# 1_P1_schdoc.net
KiCad netlist of a schematic drawn in Altium Designer
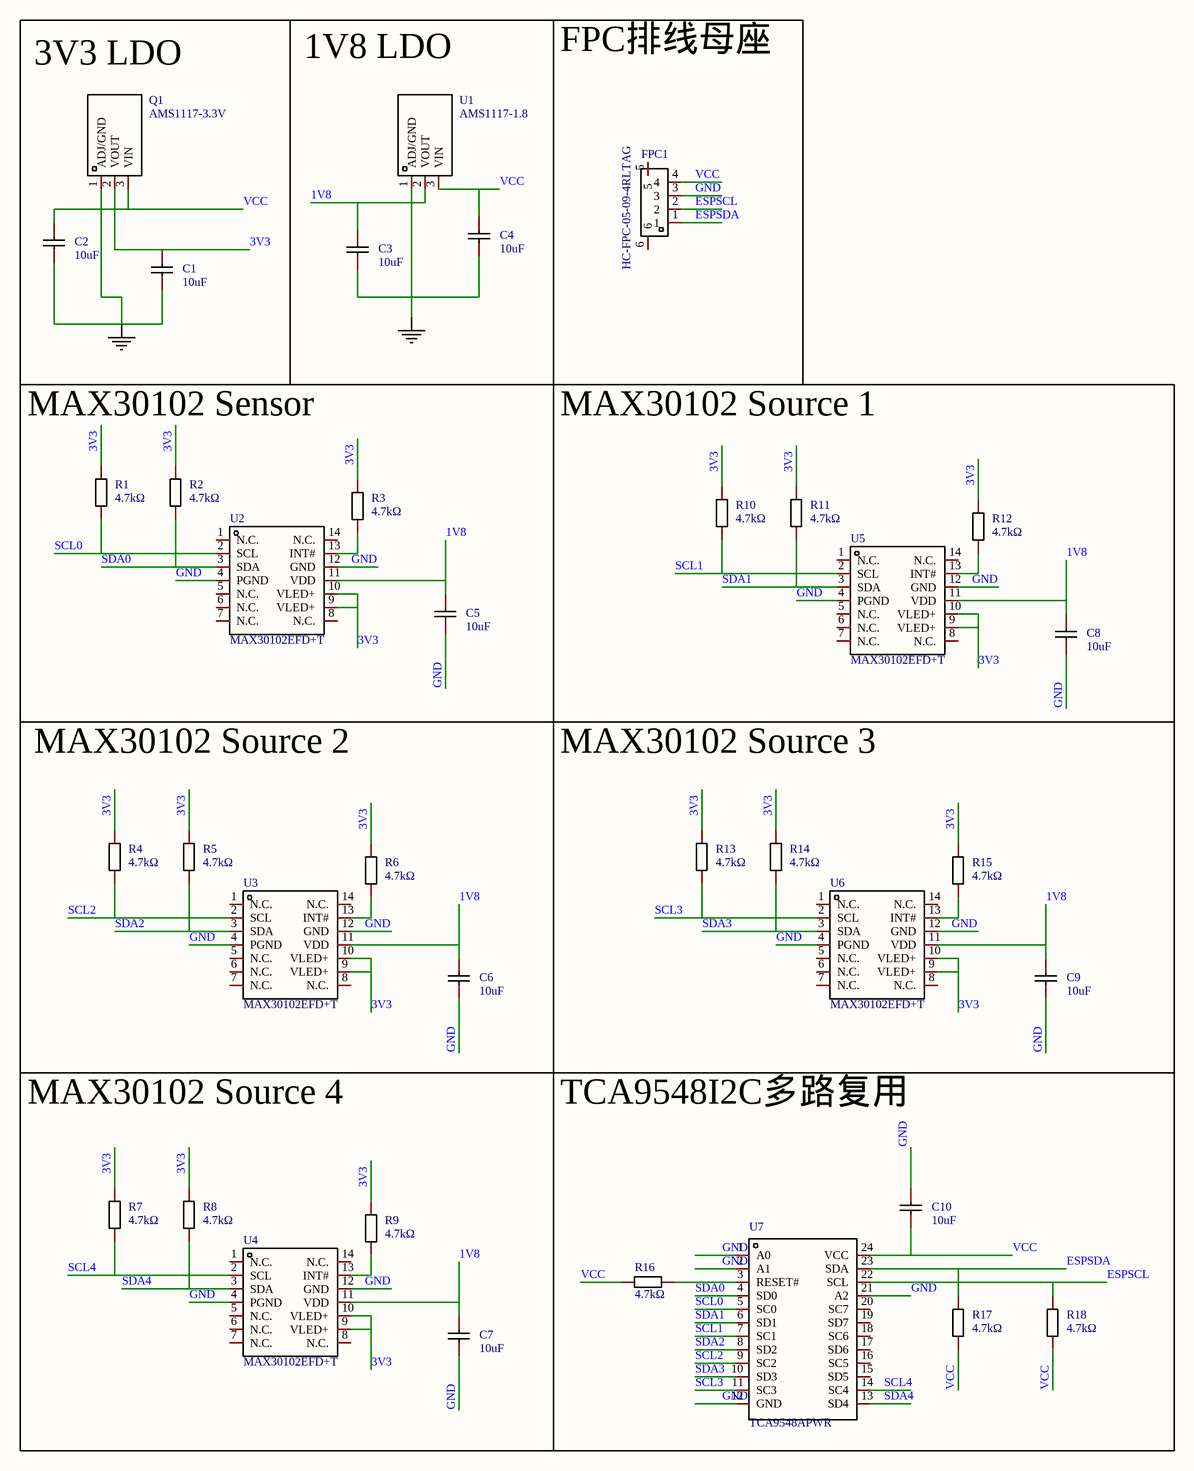
[diagram p0: 1_P1.schdoc.schdoc]

(export (version "E")
  (design (tool "Eeschema 10.0.6"))
  (components
    (comp (ref "C1")
      (value "10uF")
      (fields
        (field (name "NAME") "10uF")
        (field (name "MANUFACTURER PART") "CL05A106MQ5NUNC")
        (field (name "MANUFACTURER") "SAMSUNG(三星)")
        (field (name "TOLERANCE") "±20%")
      )
      (libsource (lib "altium-import") (part "root_1_CL05A106MQ5NUNC_"))
    )
    (comp (ref "C2")
      (value "10uF")
      (fields
        (field (name "NAME") "10uF")
        (field (name "MANUFACTURER PART") "CL05A106MQ5NUNC")
        (field (name "MANUFACTURER") "SAMSUNG(三星)")
        (field (name "TOLERANCE") "±20%")
      )
      (libsource (lib "altium-import") (part "root_1_CL05A106MQ5NUNC_"))
    )
    (comp (ref "C3")
      (value "10uF")
      (fields
        (field (name "NAME") "10uF")
        (field (name "MANUFACTURER PART") "CL05A106MQ5NUNC")
        (field (name "MANUFACTURER") "SAMSUNG(三星)")
        (field (name "TOLERANCE") "±20%")
      )
      (libsource (lib "altium-import") (part "root_1_CL05A106MQ5NUNC_"))
    )
    (comp (ref "C4")
      (value "10uF")
      (fields
        (field (name "NAME") "10uF")
        (field (name "MANUFACTURER PART") "CL05A106MQ5NUNC")
        (field (name "MANUFACTURER") "SAMSUNG(三星)")
        (field (name "TOLERANCE") "±20%")
      )
      (libsource (lib "altium-import") (part "root_1_CL05A106MQ5NUNC_"))
    )
    (comp (ref "C5")
      (value "10uF")
      (fields
        (field (name "NAME") "10uF")
        (field (name "MANUFACTURER PART") "CL05A106MQ5NUNC")
        (field (name "MANUFACTURER") "SAMSUNG(三星)")
        (field (name "TOLERANCE") "±20%")
      )
      (libsource (lib "altium-import") (part "root_1_CL05A106MQ5NUNC_"))
    )
    (comp (ref "C6")
      (value "10uF")
      (fields
        (field (name "NAME") "10uF")
        (field (name "MANUFACTURER PART") "CL05A106MQ5NUNC")
        (field (name "MANUFACTURER") "SAMSUNG(三星)")
        (field (name "TOLERANCE") "±20%")
      )
      (libsource (lib "altium-import") (part "root_3_CL05A106MQ5NUNC_"))
    )
    (comp (ref "C7")
      (value "10uF")
      (fields
        (field (name "NAME") "10uF")
        (field (name "MANUFACTURER PART") "CL05A106MQ5NUNC")
        (field (name "MANUFACTURER") "SAMSUNG(三星)")
        (field (name "TOLERANCE") "±20%")
      )
      (libsource (lib "altium-import") (part "root_1_CL05A106MQ5NUNC_"))
    )
    (comp (ref "C8")
      (value "10uF")
      (fields
        (field (name "NAME") "10uF")
        (field (name "MANUFACTURER PART") "CL05A106MQ5NUNC")
        (field (name "MANUFACTURER") "SAMSUNG(三星)")
        (field (name "TOLERANCE") "±20%")
      )
      (libsource (lib "altium-import") (part "root_1_CL05A106MQ5NUNC_"))
    )
    (comp (ref "C9")
      (value "10uF")
      (fields
        (field (name "NAME") "10uF")
        (field (name "MANUFACTURER PART") "CL05A106MQ5NUNC")
        (field (name "MANUFACTURER") "SAMSUNG(三星)")
        (field (name "TOLERANCE") "±20%")
      )
      (libsource (lib "altium-import") (part "root_1_CL05A106MQ5NUNC_"))
    )
    (comp (ref "C10")
      (value "10uF")
      (fields
        (field (name "NAME") "10uF")
        (field (name "MANUFACTURER PART") "CL05A106MQ5NUNC")
        (field (name "MANUFACTURER") "SAMSUNG(三星)")
        (field (name "TOLERANCE") "±20%")
      )
      (libsource (lib "altium-import") (part "root_1_CL05A106MQ5NUNC_"))
    )
    (comp (ref "FPC1")
      (value "HC-FPC-05-09-4RLTAG")
      (description "锁定特性:翻盖式;触点类型:双侧触点/上下接;触点数量:4P;间距:0.5mm;安装类型:卧贴;工作温度范围:-;焊接温度(最大值):-;")
      (fields (field (name "NAME") "HC-FPC-05-09-4RLTAG") (field (name "MANUFACTURER") "HCTL(华灿天禄)"))
      (libsource (lib "altium-import") (part "root_2_HC-FPC-05-09-4RLTAG_"))
    )
    (comp (ref "Q1")
      (value "AMS1117-3.3V")
      (description "输出类型:固定;最大输入电压:18V;输出电压:3.3V;最大输出电流:1A;输出极性:正极;")
      (fields (field (name "NAME") "AMS1117-3.3V") (field (name "MANUFACTURER") "MSKSEMI(美森科)"))
      (libsource (lib "altium-import") (part "root_1_AMS1117-3.3V_C5120796_"))
    )
    (comp (ref "R1")
      (value "4.7kΩ")
      (fields
        (field (name "NAME") "4.7kΩ")
        (field (name "MANUFACTURER") "UNI-ROYAL(厚声)")
        (field (name "MANUFACTURER PART") "0402WGF4701TCE")
        (field (name "TOLERANCE") "±1%")
      )
      (libsource (lib "altium-import") (part "root_1_0402WGF4701TCE_"))
    )
    (comp (ref "R2")
      (value "4.7kΩ")
      (fields
        (field (name "NAME") "4.7kΩ")
        (field (name "MANUFACTURER") "UNI-ROYAL(厚声)")
        (field (name "MANUFACTURER PART") "0402WGF4701TCE")
        (field (name "TOLERANCE") "±1%")
      )
      (libsource (lib "altium-import") (part "root_1_0402WGF4701TCE_"))
    )
    (comp (ref "R3")
      (value "4.7kΩ")
      (fields
        (field (name "NAME") "4.7kΩ")
        (field (name "MANUFACTURER") "UNI-ROYAL(厚声)")
        (field (name "MANUFACTURER PART") "0402WGF4701TCE")
        (field (name "TOLERANCE") "±1%")
      )
      (libsource (lib "altium-import") (part "root_1_0402WGF4701TCE_"))
    )
    (comp (ref "R4")
      (value "4.7kΩ")
      (fields
        (field (name "NAME") "4.7kΩ")
        (field (name "MANUFACTURER") "UNI-ROYAL(厚声)")
        (field (name "MANUFACTURER PART") "0402WGF4701TCE")
        (field (name "TOLERANCE") "±1%")
      )
      (libsource (lib "altium-import") (part "root_1_0402WGF4701TCE_"))
    )
    (comp (ref "R5")
      (value "4.7kΩ")
      (fields
        (field (name "NAME") "4.7kΩ")
        (field (name "MANUFACTURER") "UNI-ROYAL(厚声)")
        (field (name "MANUFACTURER PART") "0402WGF4701TCE")
        (field (name "TOLERANCE") "±1%")
      )
      (libsource (lib "altium-import") (part "root_1_0402WGF4701TCE_"))
    )
    (comp (ref "R6")
      (value "4.7kΩ")
      (fields
        (field (name "NAME") "4.7kΩ")
        (field (name "MANUFACTURER") "UNI-ROYAL(厚声)")
        (field (name "MANUFACTURER PART") "0402WGF4701TCE")
        (field (name "TOLERANCE") "±1%")
      )
      (libsource (lib "altium-import") (part "root_1_0402WGF4701TCE_"))
    )
    (comp (ref "R7")
      (value "4.7kΩ")
      (fields
        (field (name "NAME") "4.7kΩ")
        (field (name "MANUFACTURER") "UNI-ROYAL(厚声)")
        (field (name "MANUFACTURER PART") "0402WGF4701TCE")
        (field (name "TOLERANCE") "±1%")
      )
      (libsource (lib "altium-import") (part "root_1_0402WGF4701TCE_"))
    )
    (comp (ref "R8")
      (value "4.7kΩ")
      (fields
        (field (name "NAME") "4.7kΩ")
        (field (name "MANUFACTURER") "UNI-ROYAL(厚声)")
        (field (name "MANUFACTURER PART") "0402WGF4701TCE")
        (field (name "TOLERANCE") "±1%")
      )
      (libsource (lib "altium-import") (part "root_1_0402WGF4701TCE_"))
    )
    (comp (ref "R9")
      (value "4.7kΩ")
      (fields
        (field (name "NAME") "4.7kΩ")
        (field (name "MANUFACTURER") "UNI-ROYAL(厚声)")
        (field (name "MANUFACTURER PART") "0402WGF4701TCE")
        (field (name "TOLERANCE") "±1%")
      )
      (libsource (lib "altium-import") (part "root_1_0402WGF4701TCE_"))
    )
    (comp (ref "R10")
      (value "4.7kΩ")
      (fields
        (field (name "NAME") "4.7kΩ")
        (field (name "MANUFACTURER") "UNI-ROYAL(厚声)")
        (field (name "MANUFACTURER PART") "0402WGF4701TCE")
        (field (name "TOLERANCE") "±1%")
      )
      (libsource (lib "altium-import") (part "root_1_0402WGF4701TCE_"))
    )
    (comp (ref "R11")
      (value "4.7kΩ")
      (fields
        (field (name "NAME") "4.7kΩ")
        (field (name "MANUFACTURER") "UNI-ROYAL(厚声)")
        (field (name "MANUFACTURER PART") "0402WGF4701TCE")
        (field (name "TOLERANCE") "±1%")
      )
      (libsource (lib "altium-import") (part "root_1_0402WGF4701TCE_"))
    )
    (comp (ref "R12")
      (value "4.7kΩ")
      (fields
        (field (name "NAME") "4.7kΩ")
        (field (name "MANUFACTURER") "UNI-ROYAL(厚声)")
        (field (name "MANUFACTURER PART") "0402WGF4701TCE")
        (field (name "TOLERANCE") "±1%")
      )
      (libsource (lib "altium-import") (part "root_1_0402WGF4701TCE_"))
    )
    (comp (ref "R13")
      (value "4.7kΩ")
      (fields
        (field (name "NAME") "4.7kΩ")
        (field (name "MANUFACTURER") "UNI-ROYAL(厚声)")
        (field (name "MANUFACTURER PART") "0402WGF4701TCE")
        (field (name "TOLERANCE") "±1%")
      )
      (libsource (lib "altium-import") (part "root_1_0402WGF4701TCE_"))
    )
    (comp (ref "R14")
      (value "4.7kΩ")
      (fields
        (field (name "NAME") "4.7kΩ")
        (field (name "MANUFACTURER") "UNI-ROYAL(厚声)")
        (field (name "MANUFACTURER PART") "0402WGF4701TCE")
        (field (name "TOLERANCE") "±1%")
      )
      (libsource (lib "altium-import") (part "root_1_0402WGF4701TCE_"))
    )
    (comp (ref "R15")
      (value "4.7kΩ")
      (fields
        (field (name "NAME") "4.7kΩ")
        (field (name "MANUFACTURER") "UNI-ROYAL(厚声)")
        (field (name "MANUFACTURER PART") "0402WGF4701TCE")
        (field (name "TOLERANCE") "±1%")
      )
      (libsource (lib "altium-import") (part "root_1_0402WGF4701TCE_"))
    )
    (comp (ref "R16")
      (value "4.7kΩ")
      (fields
        (field (name "NAME") "4.7kΩ")
        (field (name "MANUFACTURER") "UNI-ROYAL(厚声)")
        (field (name "MANUFACTURER PART") "0402WGF4701TCE")
        (field (name "TOLERANCE") "±1%")
      )
      (libsource (lib "altium-import") (part "root_0_0402WGF4701TCE_"))
    )
    (comp (ref "R17")
      (value "4.7kΩ")
      (fields
        (field (name "NAME") "4.7kΩ")
        (field (name "MANUFACTURER") "UNI-ROYAL(厚声)")
        (field (name "MANUFACTURER PART") "0402WGF4701TCE")
        (field (name "TOLERANCE") "±1%")
      )
      (libsource (lib "altium-import") (part "root_1_0402WGF4701TCE_"))
    )
    (comp (ref "R18")
      (value "4.7kΩ")
      (fields
        (field (name "NAME") "4.7kΩ")
        (field (name "MANUFACTURER") "UNI-ROYAL(厚声)")
        (field (name "MANUFACTURER PART") "0402WGF4701TCE")
        (field (name "TOLERANCE") "±1%")
      )
      (libsource (lib "altium-import") (part "root_1_0402WGF4701TCE_"))
    )
    (comp (ref "U1")
      (value "AMS1117-1.8")
      (description "输出类型:-;")
      (fields (field (name "NAME") "AMS1117-1.8") (field (name "MANUFACTURER") "Slkor(萨科微)"))
      (libsource (lib "altium-import") (part "root_1_AMS1117-1.8_C880751_"))
    )
    (comp (ref "U2")
      (value "MAX30102EFD+T")
      (fields (field (name "NAME") "MAX30102EFD+T") (field (name "MANUFACTURER") "ADI(亚德诺)/MAXIM(美信)"))
      (libsource (lib "altium-import") (part "root_0_MAX30102EFD+T_1_"))
    )
    (comp (ref "U3")
      (value "MAX30102EFD+T")
      (fields (field (name "NAME") "MAX30102EFD+T") (field (name "MANUFACTURER") "ADI(亚德诺)/MAXIM(美信)"))
      (libsource (lib "altium-import") (part "root_0_MAX30102EFD+T_1_"))
    )
    (comp (ref "U4")
      (value "MAX30102EFD+T")
      (fields (field (name "NAME") "MAX30102EFD+T") (field (name "MANUFACTURER") "ADI(亚德诺)/MAXIM(美信)"))
      (libsource (lib "altium-import") (part "root_0_MAX30102EFD+T_1_"))
    )
    (comp (ref "U5")
      (value "MAX30102EFD+T")
      (fields (field (name "NAME") "MAX30102EFD+T") (field (name "MANUFACTURER") "ADI(亚德诺)/MAXIM(美信)"))
      (libsource (lib "altium-import") (part "root_0_MAX30102EFD+T_1_"))
    )
    (comp (ref "U6")
      (value "MAX30102EFD+T")
      (fields (field (name "NAME") "MAX30102EFD+T") (field (name "MANUFACTURER") "ADI(亚德诺)/MAXIM(美信)"))
      (libsource (lib "altium-import") (part "root_0_MAX30102EFD+T_1_"))
    )
    (comp (ref "U7")
      (value "TCA9548APWR")
      (description "类型:总线开关;电压-电源:1.65V ~ 5.5V;电路:1 x 8：1;电压源:单电源;逻辑电路的归属系列:TCA;")
      (fields (field (name "NAME") "TCA9548APWR") (field (name "MANUFACTURER") "TI(德州仪器)"))
      (libsource (lib "altium-import") (part "root_0_TCA9548APWR_"))
    )
  )
  (nets
    (net (code "1") (name "/1V8") (class "Default")
      (node (ref "C3") (pin "2") (pinfunction "2_2") (pintype "passive"))
      (node (ref "C5") (pin "2") (pinfunction "2_2") (pintype "passive"))
      (node (ref "C6") (pin "1") (pinfunction "1_1") (pintype "passive"))
      (node (ref "C7") (pin "2") (pinfunction "2_2") (pintype "passive"))
      (node (ref "C8") (pin "2") (pinfunction "2_2") (pintype "passive"))
      (node (ref "C9") (pin "2") (pinfunction "2_2") (pintype "passive"))
      (node (ref "U1") (pin "2") (pinfunction "VOUT_2") (pintype "passive"))
      (node (ref "U2") (pin "11") (pinfunction "VDD_11") (pintype "passive"))
      (node (ref "U3") (pin "11") (pinfunction "VDD_11") (pintype "passive"))
      (node (ref "U4") (pin "11") (pinfunction "VDD_11") (pintype "passive"))
      (node (ref "U5") (pin "11") (pinfunction "VDD_11") (pintype "passive"))
      (node (ref "U6") (pin "11") (pinfunction "VDD_11") (pintype "passive"))
    )
    (net (code "2") (name "/3V3") (class "Default")
      (node (ref "C1") (pin "2") (pinfunction "2_2") (pintype "passive"))
      (node (ref "Q1") (pin "2") (pinfunction "VOUT_2") (pintype "passive"))
      (node (ref "R1") (pin "2") (pinfunction "2_2") (pintype "passive"))
      (node (ref "R10") (pin "2") (pinfunction "2_2") (pintype "passive"))
      (node (ref "R11") (pin "2") (pinfunction "2_2") (pintype "passive"))
      (node (ref "R12") (pin "2") (pinfunction "2_2") (pintype "passive"))
      (node (ref "R13") (pin "2") (pinfunction "2_2") (pintype "passive"))
      (node (ref "R14") (pin "2") (pinfunction "2_2") (pintype "passive"))
      (node (ref "R15") (pin "2") (pinfunction "2_2") (pintype "passive"))
      (node (ref "R2") (pin "2") (pinfunction "2_2") (pintype "passive"))
      (node (ref "R3") (pin "2") (pinfunction "2_2") (pintype "passive"))
      (node (ref "R4") (pin "2") (pinfunction "2_2") (pintype "passive"))
      (node (ref "R5") (pin "2") (pinfunction "2_2") (pintype "passive"))
      (node (ref "R6") (pin "2") (pinfunction "2_2") (pintype "passive"))
      (node (ref "R7") (pin "2") (pinfunction "2_2") (pintype "passive"))
      (node (ref "R8") (pin "2") (pinfunction "2_2") (pintype "passive"))
      (node (ref "R9") (pin "2") (pinfunction "2_2") (pintype "passive"))
      (node (ref "U2") (pin "10") (pinfunction "VLED+_10") (pintype "passive"))
      (node (ref "U2") (pin "9") (pinfunction "VLED+_9") (pintype "passive"))
      (node (ref "U3") (pin "10") (pinfunction "VLED+_10") (pintype "passive"))
      (node (ref "U3") (pin "9") (pinfunction "VLED+_9") (pintype "passive"))
      (node (ref "U4") (pin "10") (pinfunction "VLED+_10") (pintype "passive"))
      (node (ref "U4") (pin "9") (pinfunction "VLED+_9") (pintype "passive"))
      (node (ref "U5") (pin "10") (pinfunction "VLED+_10") (pintype "passive"))
      (node (ref "U5") (pin "9") (pinfunction "VLED+_9") (pintype "passive"))
      (node (ref "U6") (pin "10") (pinfunction "VLED+_10") (pintype "passive"))
      (node (ref "U6") (pin "9") (pinfunction "VLED+_9") (pintype "passive"))
    )
    (net (code "3") (name "/ESPSCL") (class "Default")
      (node (ref "FPC1") (pin "2") (pinfunction "2_2") (pintype "passive"))
      (node (ref "R18") (pin "2") (pinfunction "2_2") (pintype "passive"))
      (node (ref "U7") (pin "22") (pinfunction "SCL_22") (pintype "passive"))
    )
    (net (code "4") (name "/ESPSDA") (class "Default")
      (node (ref "FPC1") (pin "1") (pinfunction "1_1") (pintype "passive"))
      (node (ref "R17") (pin "2") (pinfunction "2_2") (pintype "passive"))
      (node (ref "U7") (pin "23") (pinfunction "SDA_23") (pintype "passive"))
    )
    (net (code "5") (name "/GND") (class "Default")
      (node (ref "C10") (pin "2") (pinfunction "2_2") (pintype "passive"))
      (node (ref "C5") (pin "1") (pinfunction "1_1") (pintype "passive"))
      (node (ref "C6") (pin "2") (pinfunction "2_2") (pintype "passive"))
      (node (ref "C7") (pin "1") (pinfunction "1_1") (pintype "passive"))
      (node (ref "C8") (pin "1") (pinfunction "1_1") (pintype "passive"))
      (node (ref "C9") (pin "1") (pinfunction "1_1") (pintype "passive"))
      (node (ref "FPC1") (pin "3") (pinfunction "3_3") (pintype "passive"))
      (node (ref "U2") (pin "12") (pinfunction "GND_12") (pintype "passive"))
      (node (ref "U2") (pin "4") (pinfunction "PGND_4") (pintype "passive"))
      (node (ref "U3") (pin "12") (pinfunction "GND_12") (pintype "passive"))
      (node (ref "U3") (pin "4") (pinfunction "PGND_4") (pintype "passive"))
      (node (ref "U4") (pin "12") (pinfunction "GND_12") (pintype "passive"))
      (node (ref "U4") (pin "4") (pinfunction "PGND_4") (pintype "passive"))
      (node (ref "U5") (pin "12") (pinfunction "GND_12") (pintype "passive"))
      (node (ref "U5") (pin "4") (pinfunction "PGND_4") (pintype "passive"))
      (node (ref "U6") (pin "12") (pinfunction "GND_12") (pintype "passive"))
      (node (ref "U6") (pin "4") (pinfunction "PGND_4") (pintype "passive"))
      (node (ref "U7") (pin "1") (pinfunction "A0_1") (pintype "passive"))
      (node (ref "U7") (pin "12") (pinfunction "GND_12") (pintype "passive"))
      (node (ref "U7") (pin "2") (pinfunction "A1_2") (pintype "passive"))
      (node (ref "U7") (pin "21") (pinfunction "A2_21") (pintype "passive"))
    )
    (net (code "6") (name "/SCL0") (class "Default")
      (node (ref "R1") (pin "1") (pinfunction "1_1") (pintype "passive"))
      (node (ref "U2") (pin "2") (pinfunction "SCL_2") (pintype "passive"))
      (node (ref "U7") (pin "5") (pinfunction "SC0_5") (pintype "passive"))
    )
    (net (code "7") (name "/SCL1") (class "Default")
      (node (ref "R10") (pin "1") (pinfunction "1_1") (pintype "passive"))
      (node (ref "U5") (pin "2") (pinfunction "SCL_2") (pintype "passive"))
      (node (ref "U7") (pin "7") (pinfunction "SC1_7") (pintype "passive"))
    )
    (net (code "8") (name "/SCL2") (class "Default")
      (node (ref "R4") (pin "1") (pinfunction "1_1") (pintype "passive"))
      (node (ref "U3") (pin "2") (pinfunction "SCL_2") (pintype "passive"))
      (node (ref "U7") (pin "9") (pinfunction "SC2_9") (pintype "passive"))
    )
    (net (code "9") (name "/SCL3") (class "Default")
      (node (ref "R13") (pin "1") (pinfunction "1_1") (pintype "passive"))
      (node (ref "U6") (pin "2") (pinfunction "SCL_2") (pintype "passive"))
      (node (ref "U7") (pin "11") (pinfunction "SC3_11") (pintype "passive"))
    )
    (net (code "10") (name "/SCL4") (class "Default")
      (node (ref "R7") (pin "1") (pinfunction "1_1") (pintype "passive"))
      (node (ref "U4") (pin "2") (pinfunction "SCL_2") (pintype "passive"))
      (node (ref "U7") (pin "14") (pinfunction "SC4_14") (pintype "passive"))
    )
    (net (code "11") (name "/SDA0") (class "Default")
      (node (ref "R2") (pin "1") (pinfunction "1_1") (pintype "passive"))
      (node (ref "U2") (pin "3") (pinfunction "SDA_3") (pintype "passive"))
      (node (ref "U7") (pin "4") (pinfunction "SD0_4") (pintype "passive"))
    )
    (net (code "12") (name "/SDA1") (class "Default")
      (node (ref "R11") (pin "1") (pinfunction "1_1") (pintype "passive"))
      (node (ref "U5") (pin "3") (pinfunction "SDA_3") (pintype "passive"))
      (node (ref "U7") (pin "6") (pinfunction "SD1_6") (pintype "passive"))
    )
    (net (code "13") (name "/SDA2") (class "Default")
      (node (ref "R5") (pin "1") (pinfunction "1_1") (pintype "passive"))
      (node (ref "U3") (pin "3") (pinfunction "SDA_3") (pintype "passive"))
      (node (ref "U7") (pin "8") (pinfunction "SD2_8") (pintype "passive"))
    )
    (net (code "14") (name "/SDA3") (class "Default")
      (node (ref "R14") (pin "1") (pinfunction "1_1") (pintype "passive"))
      (node (ref "U6") (pin "3") (pinfunction "SDA_3") (pintype "passive"))
      (node (ref "U7") (pin "10") (pinfunction "SD3_10") (pintype "passive"))
    )
    (net (code "15") (name "/SDA4") (class "Default")
      (node (ref "R8") (pin "1") (pinfunction "1_1") (pintype "passive"))
      (node (ref "U4") (pin "3") (pinfunction "SDA_3") (pintype "passive"))
      (node (ref "U7") (pin "13") (pinfunction "SD4_13") (pintype "passive"))
    )
    (net (code "16") (name "/VCC") (class "Default")
      (node (ref "C10") (pin "1") (pinfunction "1_1") (pintype "passive"))
      (node (ref "C2") (pin "2") (pinfunction "2_2") (pintype "passive"))
      (node (ref "C4") (pin "2") (pinfunction "2_2") (pintype "passive"))
      (node (ref "FPC1") (pin "4") (pinfunction "4_4") (pintype "passive"))
      (node (ref "Q1") (pin "3") (pinfunction "VIN_3") (pintype "passive"))
      (node (ref "R16") (pin "1") (pinfunction "1_1") (pintype "passive"))
      (node (ref "R17") (pin "1") (pinfunction "1_1") (pintype "passive"))
      (node (ref "R18") (pin "1") (pinfunction "1_1") (pintype "passive"))
      (node (ref "U1") (pin "3") (pinfunction "VIN_3") (pintype "passive"))
      (node (ref "U7") (pin "24") (pinfunction "VCC_24") (pintype "passive"))
    )
    (net (code "17") (name "<NO NET>") (class "Default")
      (node (ref "C1") (pin "1") (pinfunction "1_1") (pintype "passive"))
      (node (ref "C2") (pin "1") (pinfunction "1_1") (pintype "passive"))
      (node (ref "C3") (pin "1") (pinfunction "1_1") (pintype "passive"))
      (node (ref "C4") (pin "1") (pinfunction "1_1") (pintype "passive"))
      (node (ref "Q1") (pin "1") (pinfunction "ADJ/GND_1") (pintype "passive"))
      (node (ref "U1") (pin "1") (pinfunction "ADJ/GND_1") (pintype "passive"))
    )
    (net (code "18") (name "Net-(U2-INT#)") (class "Default")
      (node (ref "R3") (pin "1") (pinfunction "1_1") (pintype "passive"))
      (node (ref "U2") (pin "13") (pinfunction "INT#_13") (pintype "passive"))
    )
    (net (code "19") (name "Net-(U3-INT#)") (class "Default")
      (node (ref "R6") (pin "1") (pinfunction "1_1") (pintype "passive"))
      (node (ref "U3") (pin "13") (pinfunction "INT#_13") (pintype "passive"))
    )
    (net (code "20") (name "Net-(U4-INT#)") (class "Default")
      (node (ref "R9") (pin "1") (pinfunction "1_1") (pintype "passive"))
      (node (ref "U4") (pin "13") (pinfunction "INT#_13") (pintype "passive"))
    )
    (net (code "21") (name "Net-(U5-INT#)") (class "Default")
      (node (ref "R12") (pin "1") (pinfunction "1_1") (pintype "passive"))
      (node (ref "U5") (pin "13") (pinfunction "INT#_13") (pintype "passive"))
    )
    (net (code "22") (name "Net-(U6-INT#)") (class "Default")
      (node (ref "R15") (pin "1") (pinfunction "1_1") (pintype "passive"))
      (node (ref "U6") (pin "13") (pinfunction "INT#_13") (pintype "passive"))
    )
    (net (code "23") (name "Net-(U7-RESET#)") (class "Default")
      (node (ref "R16") (pin "2") (pinfunction "2_2") (pintype "passive"))
      (node (ref "U7") (pin "3") (pinfunction "RESET#_3") (pintype "passive"))
    )
    (net (code "24") (name "unconnected-(FPC1-Pad5)") (class "Default")
      (node (ref "FPC1") (pin "5") (pinfunction "5_5") (pintype "passive"))
    )
    (net (code "25") (name "unconnected-(FPC1-Pad6)") (class "Default")
      (node (ref "FPC1") (pin "6") (pinfunction "6_6") (pintype "passive"))
    )
    (net (code "26") (name "unconnected-(U2-N.C.-Pad1)") (class "Default")
      (node (ref "U2") (pin "1") (pinfunction "N.C._1") (pintype "passive"))
    )
    (net (code "27") (name "unconnected-(U2-N.C.-Pad5)") (class "Default")
      (node (ref "U2") (pin "5") (pinfunction "N.C._5") (pintype "passive"))
    )
    (net (code "28") (name "unconnected-(U2-N.C.-Pad6)") (class "Default")
      (node (ref "U2") (pin "6") (pinfunction "N.C._6") (pintype "passive"))
    )
    (net (code "29") (name "unconnected-(U2-N.C.-Pad7)") (class "Default")
      (node (ref "U2") (pin "7") (pinfunction "N.C._7") (pintype "passive"))
    )
    (net (code "30") (name "unconnected-(U2-N.C.-Pad8)") (class "Default")
      (node (ref "U2") (pin "8") (pinfunction "N.C._8") (pintype "passive"))
    )
    (net (code "31") (name "unconnected-(U2-N.C.-Pad14)") (class "Default")
      (node (ref "U2") (pin "14") (pinfunction "N.C._14") (pintype "passive"))
    )
    (net (code "32") (name "unconnected-(U3-N.C.-Pad1)") (class "Default")
      (node (ref "U3") (pin "1") (pinfunction "N.C._1") (pintype "passive"))
    )
    (net (code "33") (name "unconnected-(U3-N.C.-Pad5)") (class "Default")
      (node (ref "U3") (pin "5") (pinfunction "N.C._5") (pintype "passive"))
    )
    (net (code "34") (name "unconnected-(U3-N.C.-Pad6)") (class "Default")
      (node (ref "U3") (pin "6") (pinfunction "N.C._6") (pintype "passive"))
    )
    (net (code "35") (name "unconnected-(U3-N.C.-Pad7)") (class "Default")
      (node (ref "U3") (pin "7") (pinfunction "N.C._7") (pintype "passive"))
    )
    (net (code "36") (name "unconnected-(U3-N.C.-Pad8)") (class "Default")
      (node (ref "U3") (pin "8") (pinfunction "N.C._8") (pintype "passive"))
    )
    (net (code "37") (name "unconnected-(U3-N.C.-Pad14)") (class "Default")
      (node (ref "U3") (pin "14") (pinfunction "N.C._14") (pintype "passive"))
    )
    (net (code "38") (name "unconnected-(U4-N.C.-Pad1)") (class "Default")
      (node (ref "U4") (pin "1") (pinfunction "N.C._1") (pintype "passive"))
    )
    (net (code "39") (name "unconnected-(U4-N.C.-Pad5)") (class "Default")
      (node (ref "U4") (pin "5") (pinfunction "N.C._5") (pintype "passive"))
    )
    (net (code "40") (name "unconnected-(U4-N.C.-Pad6)") (class "Default")
      (node (ref "U4") (pin "6") (pinfunction "N.C._6") (pintype "passive"))
    )
    (net (code "41") (name "unconnected-(U4-N.C.-Pad7)") (class "Default")
      (node (ref "U4") (pin "7") (pinfunction "N.C._7") (pintype "passive"))
    )
    (net (code "42") (name "unconnected-(U4-N.C.-Pad8)") (class "Default")
      (node (ref "U4") (pin "8") (pinfunction "N.C._8") (pintype "passive"))
    )
    (net (code "43") (name "unconnected-(U4-N.C.-Pad14)") (class "Default")
      (node (ref "U4") (pin "14") (pinfunction "N.C._14") (pintype "passive"))
    )
    (net (code "44") (name "unconnected-(U5-N.C.-Pad1)") (class "Default")
      (node (ref "U5") (pin "1") (pinfunction "N.C._1") (pintype "passive"))
    )
    (net (code "45") (name "unconnected-(U5-N.C.-Pad5)") (class "Default")
      (node (ref "U5") (pin "5") (pinfunction "N.C._5") (pintype "passive"))
    )
    (net (code "46") (name "unconnected-(U5-N.C.-Pad6)") (class "Default")
      (node (ref "U5") (pin "6") (pinfunction "N.C._6") (pintype "passive"))
    )
    (net (code "47") (name "unconnected-(U5-N.C.-Pad7)") (class "Default")
      (node (ref "U5") (pin "7") (pinfunction "N.C._7") (pintype "passive"))
    )
    (net (code "48") (name "unconnected-(U5-N.C.-Pad8)") (class "Default")
      (node (ref "U5") (pin "8") (pinfunction "N.C._8") (pintype "passive"))
    )
    (net (code "49") (name "unconnected-(U5-N.C.-Pad14)") (class "Default")
      (node (ref "U5") (pin "14") (pinfunction "N.C._14") (pintype "passive"))
    )
    (net (code "50") (name "unconnected-(U6-N.C.-Pad1)") (class "Default")
      (node (ref "U6") (pin "1") (pinfunction "N.C._1") (pintype "passive"))
    )
    (net (code "51") (name "unconnected-(U6-N.C.-Pad5)") (class "Default")
      (node (ref "U6") (pin "5") (pinfunction "N.C._5") (pintype "passive"))
    )
    (net (code "52") (name "unconnected-(U6-N.C.-Pad6)") (class "Default")
      (node (ref "U6") (pin "6") (pinfunction "N.C._6") (pintype "passive"))
    )
    (net (code "53") (name "unconnected-(U6-N.C.-Pad7)") (class "Default")
      (node (ref "U6") (pin "7") (pinfunction "N.C._7") (pintype "passive"))
    )
    (net (code "54") (name "unconnected-(U6-N.C.-Pad8)") (class "Default")
      (node (ref "U6") (pin "8") (pinfunction "N.C._8") (pintype "passive"))
    )
    (net (code "55") (name "unconnected-(U6-N.C.-Pad14)") (class "Default")
      (node (ref "U6") (pin "14") (pinfunction "N.C._14") (pintype "passive"))
    )
    (net (code "56") (name "unconnected-(U7-SC5-Pad16)") (class "Default")
      (node (ref "U7") (pin "16") (pinfunction "SC5_16") (pintype "passive"))
    )
    (net (code "57") (name "unconnected-(U7-SC6-Pad18)") (class "Default")
      (node (ref "U7") (pin "18") (pinfunction "SC6_18") (pintype "passive"))
    )
    (net (code "58") (name "unconnected-(U7-SC7-Pad20)") (class "Default")
      (node (ref "U7") (pin "20") (pinfunction "SC7_20") (pintype "passive"))
    )
    (net (code "59") (name "unconnected-(U7-SD5-Pad15)") (class "Default")
      (node (ref "U7") (pin "15") (pinfunction "SD5_15") (pintype "passive"))
    )
    (net (code "60") (name "unconnected-(U7-SD6-Pad17)") (class "Default")
      (node (ref "U7") (pin "17") (pinfunction "SD6_17") (pintype "passive"))
    )
    (net (code "61") (name "unconnected-(U7-SD7-Pad19)") (class "Default")
      (node (ref "U7") (pin "19") (pinfunction "SD7_19") (pintype "passive"))
    )
  )
)
